# 4_Button.net
KiCad netlist of a schematic drawn in Altium Designer
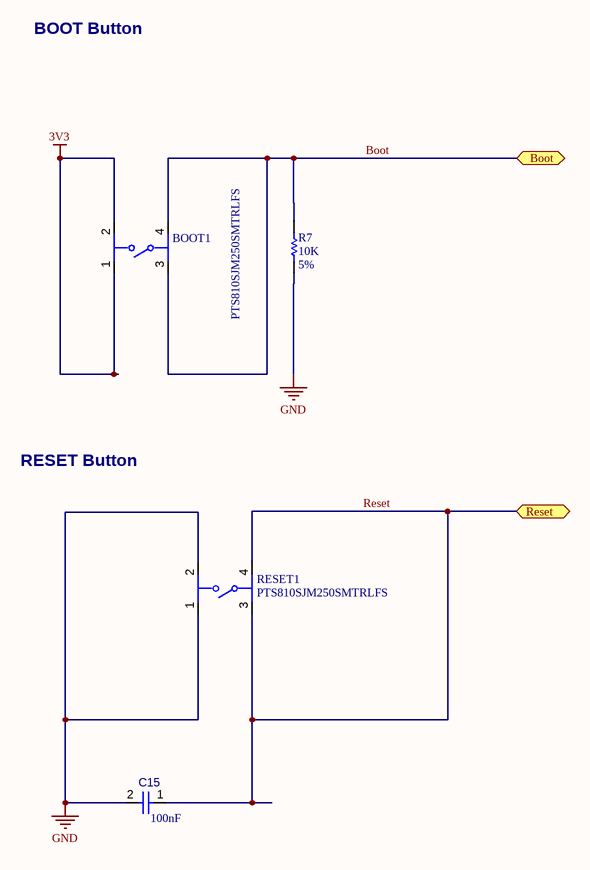
[diagram p0: [4]Button.SchDoc]

(export (version "E")
  (design (tool "Eeschema 10.0.6"))
  (components
    (comp (ref "BOOT1")
      (value "PTS810SJM250SMTRLFS")
      (footprint "FP-PTS810SJM250SMTRLFS-MFG")
      (description "SWITCH TACTILE SPST-NO 0.05A 16V")
      (fields
        (field (name "OCTOPART") "https://octopart.com/pts810+sjm+250+smtr+lfs-c%26k+components-29687929")
        (field (name "MANUFACTURER") "C&K Components")
      )
      (libsource (lib "Schlib_For_High_Voltage_Sensor") (part "Button"))
    )
    (comp (ref "C15")
      (value "100nF")
      (footprint "CAPC1608X90X40ML10T20")
      (description "Chip Capacitor, 100 nF, +/- 10%, 50 V, 0603 (1608 Metric)")
      (fields (field (name "TOLERANCE") "10%") (field (name "Comment") "Capacitor 100 nF +/-10% 50 V 0603"))
      (libsource (lib "Latium Technologies") (part "CAP-NP-2"))
    )
    (comp (ref "R7")
      (value "10K")
      (footprint "RES 0603")
      (description "RES 10K 5% 0.1W [0603]")
      (fields (field (name "TOLERANCE") "5%"))
      (libsource (lib "MasterLib") (part "RES 10K 5% 0.1W [0603]"))
    )
    (comp (ref "RESET1")
      (value "PTS810SJM250SMTRLFS")
      (footprint "FP-PTS810SJM250SMTRLFS-MFG")
      (description "SWITCH TACTILE SPST-NO 0.05A 16V")
      (fields
        (field (name "OCTOPART") "https://octopart.com/pts810+sjm+250+smtr+lfs-c%26k+components-29687929")
        (field (name "MANUFACTURER") "C&K Components")
      )
      (libsource (lib "Schlib_For_High_Voltage_Sensor") (part "Button"))
    )
  )
  (nets
    (net (code "1") (name "/Boot") (class "Default")
      (node (ref "BOOT1") (pin "3") (pinfunction "3_3") (pintype "passive"))
      (node (ref "BOOT1") (pin "4") (pinfunction "4_4") (pintype "passive"))
      (node (ref "R7") (pin "2") (pinfunction "2_2") (pintype "passive"))
    )
    (net (code "2") (name "/Reset") (class "Default")
      (node (ref "C15") (pin "1") (pinfunction "1_1") (pintype "passive"))
      (node (ref "RESET1") (pin "3") (pinfunction "3_3") (pintype "passive"))
      (node (ref "RESET1") (pin "4") (pinfunction "4_4") (pintype "passive"))
    )
    (net (code "3") (name "3V3") (class "Default")
      (node (ref "BOOT1") (pin "1") (pinfunction "1_1") (pintype "passive"))
      (node (ref "BOOT1") (pin "2") (pinfunction "2_2") (pintype "passive"))
    )
    (net (code "4") (name "GND") (class "Default")
      (node (ref "C15") (pin "2") (pinfunction "2_2") (pintype "passive"))
      (node (ref "R7") (pin "1") (pinfunction "1_1") (pintype "passive"))
      (node (ref "RESET1") (pin "1") (pinfunction "1_1") (pintype "passive"))
      (node (ref "RESET1") (pin "2") (pinfunction "2_2") (pintype "passive"))
    )
  )
)
